# untitled.net
KiCad netlist of a schematic drawn in EAGLE
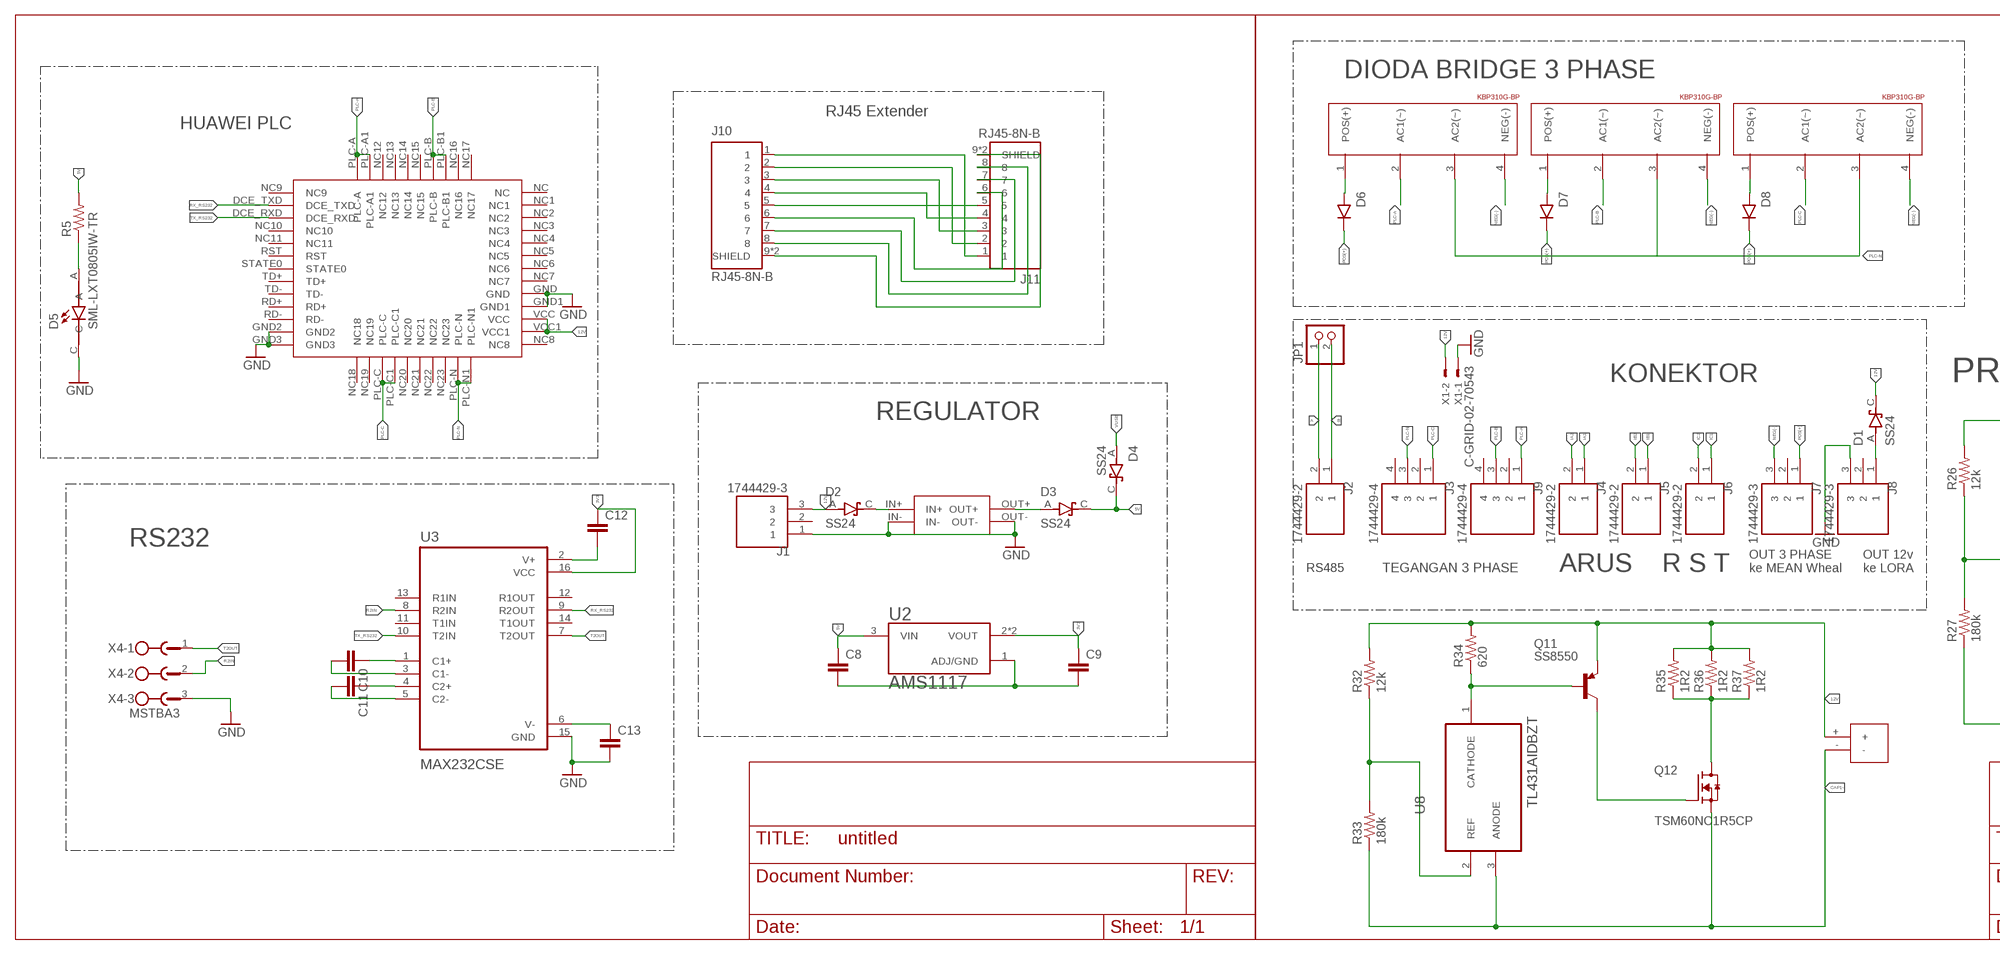
[diagram p0: schematic, sheet 1, part 1 of 2]
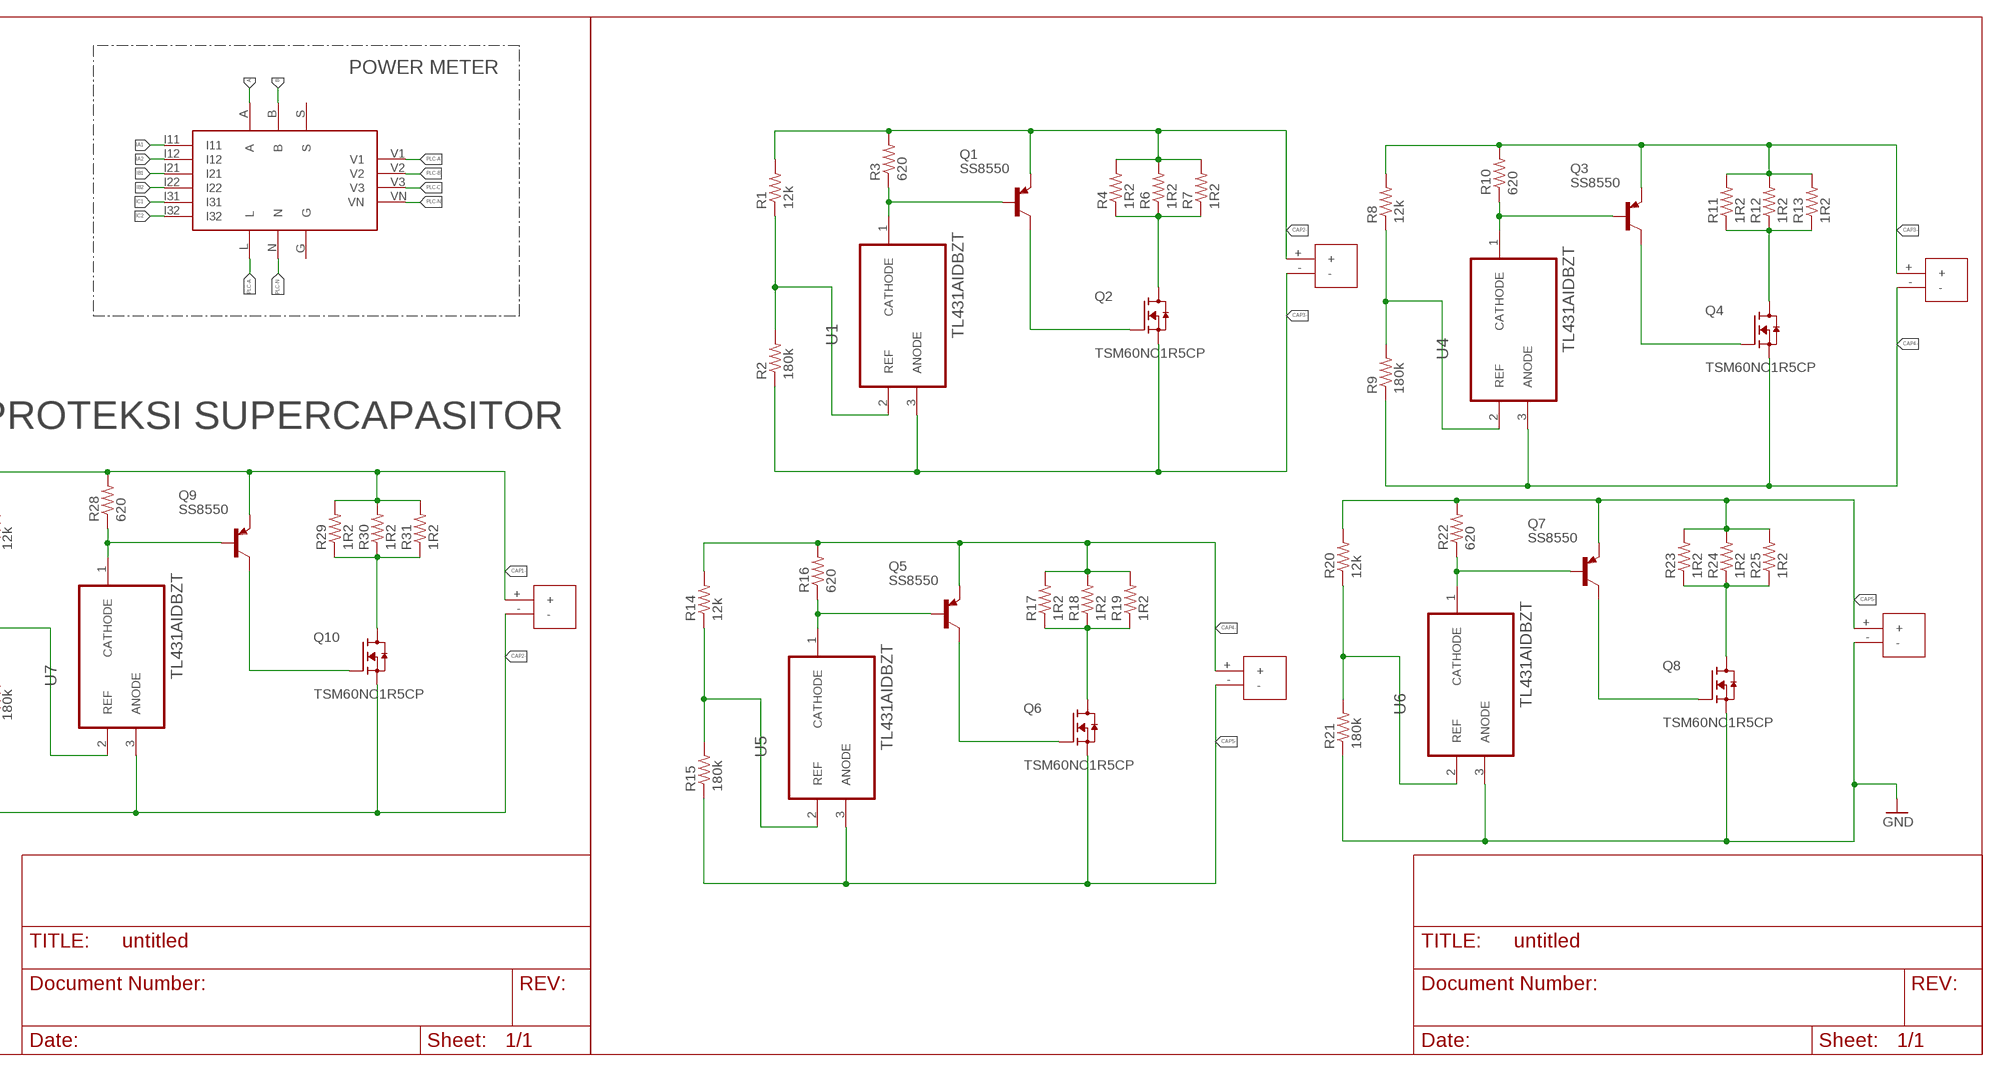
[diagram p1: schematic, sheet 1, part 2 of 2]

(export (version "E")
  (design (tool "Eeschema 10.0.6"))
  (components
    (comp (ref "C8")
      (value "C-EUC0805K")
      (footprint "eagle-import:C0805K")
      (libsource (lib "eagle-import") (part "C-EUC0805K"))
    )
    (comp (ref "C9")
      (value "C-EUC0805K")
      (footprint "eagle-import:C0805K")
      (libsource (lib "eagle-import") (part "C-EUC0805K"))
    )
    (comp (ref "C10")
      (value "C-EUC0805K")
      (footprint "eagle-import:C0805K")
      (libsource (lib "eagle-import") (part "C-EUC0805K"))
    )
    (comp (ref "C11")
      (value "C-EUC0805K")
      (footprint "eagle-import:C0805K")
      (libsource (lib "eagle-import") (part "C-EUC0805K"))
    )
    (comp (ref "C12")
      (value "C-EUC0805K")
      (footprint "eagle-import:C0805K")
      (libsource (lib "eagle-import") (part "C-EUC0805K"))
    )
    (comp (ref "C13")
      (value "C-EUC0805K")
      (footprint "eagle-import:C0805K")
      (libsource (lib "eagle-import") (part "C-EUC0805K"))
    )
    (comp (ref "D1")
      (value "SS24")
      (footprint "eagle-import:DIOM5336X265N")
      (fields (field (name "MF") "ON Semiconductor"))
      (libsource (lib "eagle-import") (part "SS24"))
    )
    (comp (ref "D2")
      (value "SS24")
      (footprint "eagle-import:DIOM5336X265N")
      (fields (field (name "MF") "ON Semiconductor"))
      (libsource (lib "eagle-import") (part "SS24"))
    )
    (comp (ref "D3")
      (value "SS24")
      (footprint "eagle-import:DIOM5336X265N")
      (fields (field (name "MF") "ON Semiconductor"))
      (libsource (lib "eagle-import") (part "SS24"))
    )
    (comp (ref "D4")
      (value "SS24")
      (footprint "eagle-import:DIOM5336X265N")
      (fields (field (name "MF") "ON Semiconductor"))
      (libsource (lib "eagle-import") (part "SS24"))
    )
    (comp (ref "D5")
      (value "SML-LXT0805IW-TR")
      (footprint "eagle-import:LEDC2012X120N")
      (fields (field (name "MF") "Lumex Opto/Components"))
      (libsource (lib "eagle-import") (part "SML-LXT0805IW-TR"))
    )
    (comp (ref "D6")
      (value "1N4001")
      (footprint "eagle-import:DO41-10")
      (fields (field (name "MF") "HVCA"))
      (libsource (lib "eagle-import") (part "1N4001"))
    )
    (comp (ref "D7")
      (value "1N4001")
      (footprint "eagle-import:DO41-10")
      (fields (field (name "MF") "HVCA"))
      (libsource (lib "eagle-import") (part "1N4001"))
    )
    (comp (ref "D8")
      (value "1N4001")
      (footprint "eagle-import:DO41-10")
      (fields (field (name "MF") "HVCA"))
      (libsource (lib "eagle-import") (part "1N4001"))
    )
    (comp (ref "HUAWEI-PLC1")
      (value "HUAWEI-PLC")
      (footprint "eagle-import:HUAWEI-PLC")
      (libsource (lib "eagle-import") (part "HUAWEI-PLC"))
    )
    (comp (ref "J1")
      (value "1744429-3")
      (footprint "eagle-import:TE_1744429-3")
      (fields (field (name "MANUFACTURER") "TE"))
      (libsource (lib "eagle-import") (part "1744429-3"))
    )
    (comp (ref "J2")
      (value "1744429-2")
      (footprint "eagle-import:TE_1744429-2")
      (fields (field (name "MF") "TE Connectivity"))
      (libsource (lib "eagle-import") (part "1744429-2"))
    )
    (comp (ref "J3")
      (value "1744429-4")
      (footprint "eagle-import:TE_1744429-4")
      (fields (field (name "MF") "TE Connectivity"))
      (libsource (lib "eagle-import") (part "1744429-4"))
    )
    (comp (ref "J4")
      (value "1744429-2")
      (footprint "eagle-import:TE_1744429-2")
      (fields (field (name "MF") "TE Connectivity"))
      (libsource (lib "eagle-import") (part "1744429-2"))
    )
    (comp (ref "J5")
      (value "1744429-2")
      (footprint "eagle-import:TE_1744429-2")
      (fields (field (name "MF") "TE Connectivity"))
      (libsource (lib "eagle-import") (part "1744429-2"))
    )
    (comp (ref "J6")
      (value "1744429-2")
      (footprint "eagle-import:TE_1744429-2")
      (fields (field (name "MF") "TE Connectivity"))
      (libsource (lib "eagle-import") (part "1744429-2"))
    )
    (comp (ref "J7")
      (value "1744429-3")
      (footprint "eagle-import:TE_1744429-3")
      (fields (field (name "MANUFACTURER") "TE"))
      (libsource (lib "eagle-import") (part "1744429-3"))
    )
    (comp (ref "J8")
      (value "1744429-3")
      (footprint "eagle-import:TE_1744429-3")
      (fields (field (name "MANUFACTURER") "TE"))
      (libsource (lib "eagle-import") (part "1744429-3"))
    )
    (comp (ref "J9")
      (value "1744429-4")
      (footprint "eagle-import:TE_1744429-4")
      (fields (field (name "MF") "TE Connectivity"))
      (libsource (lib "eagle-import") (part "1744429-4"))
    )
    (comp (ref "J10")
      (value "RJ45-8N-B")
      (footprint "eagle-import:TE_RJ45-8N-B")
      (fields (field (name "MF") "TE Connectivity"))
      (libsource (lib "eagle-import") (part "RJ45-8N-B"))
    )
    (comp (ref "J11")
      (value "RJ45-8N-B")
      (footprint "eagle-import:TE_RJ45-8N-B")
      (fields (field (name "MF") "TE Connectivity"))
      (libsource (lib "eagle-import") (part "RJ45-8N-B"))
    )
    (comp (ref "JP1")
      (value "PINHD-1X2")
      (footprint "eagle-import:1X02")
      (libsource (lib "eagle-import") (part "PINHD-1X2"))
    )
    (comp (ref "MINI1")
      (value "MINI560")
      (footprint "eagle-import:MINI560")
      (libsource (lib "eagle-import") (part "MINI560"))
    )
    (comp (ref "POWERMETER1")
      (value "POWERMETER")
      (footprint "eagle-import:POWERMETER")
      (libsource (lib "eagle-import") (part "POWERMETER"))
    )
    (comp (ref "Q1")
      (value "SS8550")
      (footprint "eagle-import:SOT-23_BEC")
      (fields (field (name "MF") "ON Semiconductor / Fairchild"))
      (libsource (lib "eagle-import") (part "SS8550"))
    )
    (comp (ref "Q2")
      (value "TSM60NC1R5CP")
      (footprint "eagle-import:TRANS_TSM60NC1R5CP")
      (fields (field (name "MF") "Taiwan Semiconductor"))
      (libsource (lib "eagle-import") (part "TSM60NC1R5CP"))
    )
    (comp (ref "Q3")
      (value "SS8550")
      (footprint "eagle-import:SOT-23_BEC")
      (fields (field (name "MF") "ON Semiconductor / Fairchild"))
      (libsource (lib "eagle-import") (part "SS8550"))
    )
    (comp (ref "Q4")
      (value "TSM60NC1R5CP")
      (footprint "eagle-import:TRANS_TSM60NC1R5CP")
      (fields (field (name "MF") "Taiwan Semiconductor"))
      (libsource (lib "eagle-import") (part "TSM60NC1R5CP"))
    )
    (comp (ref "Q5")
      (value "SS8550")
      (footprint "eagle-import:SOT-23_BEC")
      (fields (field (name "MF") "ON Semiconductor / Fairchild"))
      (libsource (lib "eagle-import") (part "SS8550"))
    )
    (comp (ref "Q6")
      (value "TSM60NC1R5CP")
      (footprint "eagle-import:TRANS_TSM60NC1R5CP")
      (fields (field (name "MF") "Taiwan Semiconductor"))
      (libsource (lib "eagle-import") (part "TSM60NC1R5CP"))
    )
    (comp (ref "Q7")
      (value "SS8550")
      (footprint "eagle-import:SOT-23_BEC")
      (fields (field (name "MF") "ON Semiconductor / Fairchild"))
      (libsource (lib "eagle-import") (part "SS8550"))
    )
    (comp (ref "Q8")
      (value "TSM60NC1R5CP")
      (footprint "eagle-import:TRANS_TSM60NC1R5CP")
      (fields (field (name "MF") "Taiwan Semiconductor"))
      (libsource (lib "eagle-import") (part "TSM60NC1R5CP"))
    )
    (comp (ref "Q9")
      (value "SS8550")
      (footprint "eagle-import:SOT-23_BEC")
      (fields (field (name "MF") "ON Semiconductor / Fairchild"))
      (libsource (lib "eagle-import") (part "SS8550"))
    )
    (comp (ref "Q10")
      (value "TSM60NC1R5CP")
      (footprint "eagle-import:TRANS_TSM60NC1R5CP")
      (fields (field (name "MF") "Taiwan Semiconductor"))
      (libsource (lib "eagle-import") (part "TSM60NC1R5CP"))
    )
    (comp (ref "Q11")
      (value "SS8550")
      (footprint "eagle-import:SOT-23_BEC")
      (fields (field (name "MF") "ON Semiconductor / Fairchild"))
      (libsource (lib "eagle-import") (part "SS8550"))
    )
    (comp (ref "Q12")
      (value "TSM60NC1R5CP")
      (footprint "eagle-import:TRANS_TSM60NC1R5CP")
      (fields (field (name "MF") "Taiwan Semiconductor"))
      (libsource (lib "eagle-import") (part "TSM60NC1R5CP"))
    )
    (comp (ref "R1")
      (value "12k")
      (footprint "eagle-import:R0805")
      (libsource (lib "eagle-import") (part "R-US_R0805"))
    )
    (comp (ref "R2")
      (value "180k")
      (footprint "eagle-import:R0805")
      (libsource (lib "eagle-import") (part "R-US_R0805"))
    )
    (comp (ref "R3")
      (value "620")
      (footprint "eagle-import:R0805")
      (libsource (lib "eagle-import") (part "R-US_R0805"))
    )
    (comp (ref "R4")
      (value "1R2")
      (footprint "eagle-import:R2512")
      (libsource (lib "eagle-import") (part "rcl_334_R-US_R2512"))
    )
    (comp (ref "R5")
      (value "R-US_M0805")
      (footprint "eagle-import:M0805")
      (libsource (lib "eagle-import") (part "R-US_M0805"))
    )
    (comp (ref "R6")
      (value "1R2")
      (footprint "eagle-import:R2512")
      (libsource (lib "eagle-import") (part "rcl_334_R-US_R2512"))
    )
    (comp (ref "R7")
      (value "1R2")
      (footprint "eagle-import:R2512")
      (libsource (lib "eagle-import") (part "rcl_334_R-US_R2512"))
    )
    (comp (ref "R8")
      (value "12k")
      (footprint "eagle-import:R0805")
      (libsource (lib "eagle-import") (part "R-US_R0805"))
    )
    (comp (ref "R9")
      (value "180k")
      (footprint "eagle-import:R0805")
      (libsource (lib "eagle-import") (part "R-US_R0805"))
    )
    (comp (ref "R10")
      (value "620")
      (footprint "eagle-import:R0805")
      (libsource (lib "eagle-import") (part "R-US_R0805"))
    )
    (comp (ref "R11")
      (value "1R2")
      (footprint "eagle-import:R2512")
      (libsource (lib "eagle-import") (part "rcl_334_R-US_R2512"))
    )
    (comp (ref "R12")
      (value "1R2")
      (footprint "eagle-import:R2512")
      (libsource (lib "eagle-import") (part "rcl_334_R-US_R2512"))
    )
    (comp (ref "R13")
      (value "1R2")
      (footprint "eagle-import:R2512")
      (libsource (lib "eagle-import") (part "rcl_334_R-US_R2512"))
    )
    (comp (ref "R14")
      (value "12k")
      (footprint "eagle-import:R0805")
      (libsource (lib "eagle-import") (part "R-US_R0805"))
    )
    (comp (ref "R15")
      (value "180k")
      (footprint "eagle-import:R0805")
      (libsource (lib "eagle-import") (part "R-US_R0805"))
    )
    (comp (ref "R16")
      (value "620")
      (footprint "eagle-import:R0805")
      (libsource (lib "eagle-import") (part "R-US_R0805"))
    )
    (comp (ref "R17")
      (value "1R2")
      (footprint "eagle-import:R2512")
      (libsource (lib "eagle-import") (part "rcl_334_R-US_R2512"))
    )
    (comp (ref "R18")
      (value "1R2")
      (footprint "eagle-import:R2512")
      (libsource (lib "eagle-import") (part "rcl_334_R-US_R2512"))
    )
    (comp (ref "R19")
      (value "1R2")
      (footprint "eagle-import:R2512")
      (libsource (lib "eagle-import") (part "rcl_334_R-US_R2512"))
    )
    (comp (ref "R20")
      (value "12k")
      (footprint "eagle-import:R0805")
      (libsource (lib "eagle-import") (part "R-US_R0805"))
    )
    (comp (ref "R21")
      (value "180k")
      (footprint "eagle-import:R0805")
      (libsource (lib "eagle-import") (part "R-US_R0805"))
    )
    (comp (ref "R22")
      (value "620")
      (footprint "eagle-import:R0805")
      (libsource (lib "eagle-import") (part "R-US_R0805"))
    )
    (comp (ref "R23")
      (value "1R2")
      (footprint "eagle-import:R2512")
      (libsource (lib "eagle-import") (part "rcl_334_R-US_R2512"))
    )
    (comp (ref "R24")
      (value "1R2")
      (footprint "eagle-import:R2512")
      (libsource (lib "eagle-import") (part "rcl_334_R-US_R2512"))
    )
    (comp (ref "R25")
      (value "1R2")
      (footprint "eagle-import:R2512")
      (libsource (lib "eagle-import") (part "rcl_334_R-US_R2512"))
    )
    (comp (ref "R26")
      (value "12k")
      (footprint "eagle-import:R0805")
      (libsource (lib "eagle-import") (part "R-US_R0805"))
    )
    (comp (ref "R27")
      (value "180k")
      (footprint "eagle-import:R0805")
      (libsource (lib "eagle-import") (part "R-US_R0805"))
    )
    (comp (ref "R28")
      (value "620")
      (footprint "eagle-import:R0805")
      (libsource (lib "eagle-import") (part "R-US_R0805"))
    )
    (comp (ref "R29")
      (value "1R2")
      (footprint "eagle-import:R2512")
      (libsource (lib "eagle-import") (part "rcl_334_R-US_R2512"))
    )
    (comp (ref "R30")
      (value "1R2")
      (footprint "eagle-import:R2512")
      (libsource (lib "eagle-import") (part "rcl_334_R-US_R2512"))
    )
    (comp (ref "R31")
      (value "1R2")
      (footprint "eagle-import:R2512")
      (libsource (lib "eagle-import") (part "rcl_334_R-US_R2512"))
    )
    (comp (ref "R32")
      (value "12k")
      (footprint "eagle-import:R0805")
      (libsource (lib "eagle-import") (part "R-US_R0805"))
    )
    (comp (ref "R33")
      (value "180k")
      (footprint "eagle-import:R0805")
      (libsource (lib "eagle-import") (part "R-US_R0805"))
    )
    (comp (ref "R34")
      (value "620")
      (footprint "eagle-import:R0805")
      (libsource (lib "eagle-import") (part "R-US_R0805"))
    )
    (comp (ref "R35")
      (value "1R2")
      (footprint "eagle-import:R2512")
      (libsource (lib "eagle-import") (part "rcl_334_R-US_R2512"))
    )
    (comp (ref "R36")
      (value "1R2")
      (footprint "eagle-import:R2512")
      (libsource (lib "eagle-import") (part "rcl_334_R-US_R2512"))
    )
    (comp (ref "R37")
      (value "1R2")
      (footprint "eagle-import:R2512")
      (libsource (lib "eagle-import") (part "rcl_334_R-US_R2512"))
    )
    (comp (ref "SUPERCAP1")
      (value "2.7/500F")
      (footprint "eagle-import:SUPERCAP")
      (libsource (lib "eagle-import") (part "SUPERCAP"))
    )
    (comp (ref "SUPERCAP2")
      (value "2.7/500F")
      (footprint "eagle-import:SUPERCAP")
      (libsource (lib "eagle-import") (part "SUPERCAP"))
    )
    (comp (ref "SUPERCAP3")
      (value "2.7/500F")
      (footprint "eagle-import:SUPERCAP")
      (libsource (lib "eagle-import") (part "SUPERCAP"))
    )
    (comp (ref "SUPERCAP4")
      (value "2.7/500F")
      (footprint "eagle-import:SUPERCAP")
      (libsource (lib "eagle-import") (part "SUPERCAP"))
    )
    (comp (ref "SUPERCAP5")
      (value "2.7/500F")
      (footprint "eagle-import:SUPERCAP")
      (libsource (lib "eagle-import") (part "SUPERCAP"))
    )
    (comp (ref "SUPERCAP6")
      (value "2.7/500F")
      (footprint "eagle-import:SUPERCAP")
      (libsource (lib "eagle-import") (part "SUPERCAP"))
    )
    (comp (ref "U$1")
      (value "KBP310G-BP")
      (footprint "eagle-import:KBP310G-BP")
      (fields (field (name "MF") "Micro Commercial"))
      (libsource (lib "eagle-import") (part "KBP310G-BP"))
    )
    (comp (ref "U$2")
      (value "KBP310G-BP")
      (footprint "eagle-import:KBP310G-BP")
      (fields (field (name "MF") "Micro Commercial"))
      (libsource (lib "eagle-import") (part "KBP310G-BP"))
    )
    (comp (ref "U$3")
      (value "KBP310G-BP")
      (footprint "eagle-import:KBP310G-BP")
      (fields (field (name "MF") "Micro Commercial"))
      (libsource (lib "eagle-import") (part "KBP310G-BP"))
    )
    (comp (ref "U1")
      (value "TL431AIDBZT")
      (footprint "eagle-import:SOT95P237X112-3N")
      (fields (field (name "MF") "Texas Instruments"))
      (libsource (lib "eagle-import") (part "TL431AIDBZT"))
    )
    (comp (ref "U2")
      (value "AMS1117")
      (footprint "eagle-import:SOT229P700X180-4N")
      (fields (field (name "MF") "Advanced Monolithic Systems"))
      (libsource (lib "eagle-import") (part "AMS1117"))
    )
    (comp (ref "U3")
      (value "MAX232CSE")
      (footprint "eagle-import:SOIC127P600X175-16N")
      (fields (field (name "MF") "Maxim Integrated"))
      (libsource (lib "eagle-import") (part "MAX232CSE"))
    )
    (comp (ref "U4")
      (value "TL431AIDBZT")
      (footprint "eagle-import:SOT95P237X112-3N")
      (fields (field (name "MF") "Texas Instruments"))
      (libsource (lib "eagle-import") (part "TL431AIDBZT"))
    )
    (comp (ref "U5")
      (value "TL431AIDBZT")
      (footprint "eagle-import:SOT95P237X112-3N")
      (fields (field (name "MF") "Texas Instruments"))
      (libsource (lib "eagle-import") (part "TL431AIDBZT"))
    )
    (comp (ref "U6")
      (value "TL431AIDBZT")
      (footprint "eagle-import:SOT95P237X112-3N")
      (fields (field (name "MF") "Texas Instruments"))
      (libsource (lib "eagle-import") (part "TL431AIDBZT"))
    )
    (comp (ref "U7")
      (value "TL431AIDBZT")
      (footprint "eagle-import:SOT95P237X112-3N")
      (fields (field (name "MF") "Texas Instruments"))
      (libsource (lib "eagle-import") (part "TL431AIDBZT"))
    )
    (comp (ref "U8")
      (value "TL431AIDBZT")
      (footprint "eagle-import:SOT95P237X112-3N")
      (fields (field (name "MF") "Texas Instruments"))
      (libsource (lib "eagle-import") (part "TL431AIDBZT"))
    )
    (comp (ref "X1")
      (value "C-GRID-02-70543")
      (footprint "eagle-import:70543-02")
      (fields (field (name "MF") "MOLEX"))
      (libsource (lib "eagle-import") (part "C-GRID-02-70543"))
    )
    (comp (ref "X4")
      (value "MSTBA3")
      (footprint "eagle-import:MSTBA3")
      (fields (field (name "MF") "FARNELL") (field (name "MPN") "1757255"))
      (libsource (lib "eagle-import") (part "MSTBA3"))
    )
  )
  (nets
    (net (code "1") (name "3V3") (class "Default")
      (node (ref "C12") (pin "1") (pinfunction "1_1") (pintype "passive"))
      (node (ref "C9") (pin "1") (pinfunction "1_1") (pintype "passive"))
      (node (ref "U2") (pin "2") (pinfunction "VOUT_2") (pintype "output"))
      (node (ref "U2") (pin "4") (pinfunction "VOUT_4") (pintype "output"))
      (node (ref "U3") (pin "16") (pinfunction "VCC_16") (pintype "power_in"))
    )
    (net (code "2") (name "5V") (class "Default")
      (node (ref "C8") (pin "1") (pinfunction "1_1") (pintype "passive"))
      (node (ref "D3") (pin "C") (pinfunction "K_C") (pintype "passive"))
      (node (ref "D4") (pin "C") (pinfunction "K_C") (pintype "passive"))
      (node (ref "R5") (pin "2") (pinfunction "2_2") (pintype "passive"))
      (node (ref "U2") (pin "3") (pinfunction "VIN_3") (pintype "input"))
    )
    (net (code "3") (name "12V") (class "Default")
      (node (ref "D1") (pin "C") (pinfunction "K_C") (pintype "passive"))
      (node (ref "D2") (pin "A") (pinfunction "A_A") (pintype "passive"))
      (node (ref "HUAWEI-PLC1") (pin "VCC") (pinfunction "VCC_VCC") (pintype "bidirectional"))
      (node (ref "HUAWEI-PLC1") (pin "VCC1") (pinfunction "VCC1_VCC1") (pintype "bidirectional"))
      (node (ref "J1") (pin "3") (pinfunction "3_3") (pintype "passive"))
      (node (ref "Q11") (pin "E") (pinfunction "E_E") (pintype "passive"))
      (node (ref "R32") (pin "2") (pinfunction "2_2") (pintype "passive"))
      (node (ref "R34") (pin "2") (pinfunction "2_2") (pintype "passive"))
      (node (ref "R35") (pin "2") (pinfunction "2_2") (pintype "passive"))
      (node (ref "R36") (pin "2") (pinfunction "2_2") (pintype "passive"))
      (node (ref "R37") (pin "2") (pinfunction "2_2") (pintype "passive"))
      (node (ref "SUPERCAP6") (pin "+") (pinfunction "+_+") (pintype "bidirectional"))
      (node (ref "X1") (pin "2") (pinfunction "S_2") (pintype "passive"))
    )
    (net (code "4") (name "A") (class "Default")
      (node (ref "J2") (pin "2") (pinfunction "2_2") (pintype "passive"))
      (node (ref "JP1") (pin "1") (pinfunction "1_1") (pintype "passive"))
      (node (ref "POWERMETER1") (pin "A") (pinfunction "A_A") (pintype "bidirectional"))
    )
    (net (code "5") (name "B") (class "Default")
      (node (ref "J2") (pin "1") (pinfunction "1_1") (pintype "passive"))
      (node (ref "JP1") (pin "2") (pinfunction "2_2") (pintype "passive"))
      (node (ref "POWERMETER1") (pin "B") (pinfunction "B_B") (pintype "bidirectional"))
    )
    (net (code "6") (name "CAP1-") (class "Default")
      (node (ref "Q12") (pin "3") (pinfunction "S_3") (pintype "passive"))
      (node (ref "Q9") (pin "E") (pinfunction "E_E") (pintype "passive"))
      (node (ref "R26") (pin "2") (pinfunction "2_2") (pintype "passive"))
      (node (ref "R28") (pin "2") (pinfunction "2_2") (pintype "passive"))
      (node (ref "R29") (pin "2") (pinfunction "2_2") (pintype "passive"))
      (node (ref "R30") (pin "2") (pinfunction "2_2") (pintype "passive"))
      (node (ref "R31") (pin "2") (pinfunction "2_2") (pintype "passive"))
      (node (ref "R33") (pin "1") (pinfunction "1_1") (pintype "passive"))
      (node (ref "SUPERCAP5") (pin "+") (pinfunction "+_+") (pintype "bidirectional"))
      (node (ref "SUPERCAP6") (pin "-") (pinfunction "-_-") (pintype "bidirectional"))
      (node (ref "U8") (pin "3") (pinfunction "ANODE_3") (pintype "passive"))
    )
    (net (code "7") (name "CAP2-") (class "Default")
      (node (ref "Q1") (pin "E") (pinfunction "E_E") (pintype "passive"))
      (node (ref "Q10") (pin "3") (pinfunction "S_3") (pintype "passive"))
      (node (ref "R1") (pin "2") (pinfunction "2_2") (pintype "passive"))
      (node (ref "R27") (pin "1") (pinfunction "1_1") (pintype "passive"))
      (node (ref "R3") (pin "2") (pinfunction "2_2") (pintype "passive"))
      (node (ref "R4") (pin "2") (pinfunction "2_2") (pintype "passive"))
      (node (ref "R6") (pin "2") (pinfunction "2_2") (pintype "passive"))
      (node (ref "R7") (pin "2") (pinfunction "2_2") (pintype "passive"))
      (node (ref "SUPERCAP1") (pin "+") (pinfunction "+_+") (pintype "bidirectional"))
      (node (ref "SUPERCAP5") (pin "-") (pinfunction "-_-") (pintype "bidirectional"))
      (node (ref "U7") (pin "3") (pinfunction "ANODE_3") (pintype "passive"))
    )
    (net (code "8") (name "CAP3-") (class "Default")
      (node (ref "Q2") (pin "3") (pinfunction "S_3") (pintype "passive"))
      (node (ref "Q3") (pin "E") (pinfunction "E_E") (pintype "passive"))
      (node (ref "R10") (pin "2") (pinfunction "2_2") (pintype "passive"))
      (node (ref "R11") (pin "2") (pinfunction "2_2") (pintype "passive"))
      (node (ref "R12") (pin "2") (pinfunction "2_2") (pintype "passive"))
      (node (ref "R13") (pin "2") (pinfunction "2_2") (pintype "passive"))
      (node (ref "R2") (pin "1") (pinfunction "1_1") (pintype "passive"))
      (node (ref "R8") (pin "2") (pinfunction "2_2") (pintype "passive"))
      (node (ref "SUPERCAP1") (pin "-") (pinfunction "-_-") (pintype "bidirectional"))
      (node (ref "SUPERCAP2") (pin "+") (pinfunction "+_+") (pintype "bidirectional"))
      (node (ref "U1") (pin "3") (pinfunction "ANODE_3") (pintype "passive"))
    )
    (net (code "9") (name "CAP4-") (class "Default")
      (node (ref "Q4") (pin "3") (pinfunction "S_3") (pintype "passive"))
      (node (ref "Q5") (pin "E") (pinfunction "E_E") (pintype "passive"))
      (node (ref "R14") (pin "2") (pinfunction "2_2") (pintype "passive"))
      (node (ref "R16") (pin "2") (pinfunction "2_2") (pintype "passive"))
      (node (ref "R17") (pin "2") (pinfunction "2_2") (pintype "passive"))
      (node (ref "R18") (pin "2") (pinfunction "2_2") (pintype "passive"))
      (node (ref "R19") (pin "2") (pinfunction "2_2") (pintype "passive"))
      (node (ref "R9") (pin "1") (pinfunction "1_1") (pintype "passive"))
      (node (ref "SUPERCAP2") (pin "-") (pinfunction "-_-") (pintype "bidirectional"))
      (node (ref "SUPERCAP3") (pin "+") (pinfunction "+_+") (pintype "bidirectional"))
      (node (ref "U4") (pin "3") (pinfunction "ANODE_3") (pintype "passive"))
    )
    (net (code "10") (name "CAP5-") (class "Default")
      (node (ref "Q6") (pin "3") (pinfunction "S_3") (pintype "passive"))
      (node (ref "Q7") (pin "E") (pinfunction "E_E") (pintype "passive"))
      (node (ref "R15") (pin "1") (pinfunction "1_1") (pintype "passive"))
      (node (ref "R20") (pin "2") (pinfunction "2_2") (pintype "passive"))
      (node (ref "R22") (pin "2") (pinfunction "2_2") (pintype "passive"))
      (node (ref "R23") (pin "2") (pinfunction "2_2") (pintype "passive"))
      (node (ref "R24") (pin "2") (pinfunction "2_2") (pintype "passive"))
      (node (ref "R25") (pin "2") (pinfunction "2_2") (pintype "passive"))
      (node (ref "SUPERCAP3") (pin "-") (pinfunction "-_-") (pintype "bidirectional"))
      (node (ref "SUPERCAP4") (pin "+") (pinfunction "+_+") (pintype "bidirectional"))
      (node (ref "U5") (pin "3") (pinfunction "ANODE_3") (pintype "passive"))
    )
    (net (code "11") (name "GND") (class "Default")
      (node (ref "C13") (pin "2") (pinfunction "2_2") (pintype "passive"))
      (node (ref "D5") (pin "C") (pinfunction "C_C") (pintype "passive"))
      (node (ref "HUAWEI-PLC1") (pin "GND") (pinfunction "GND_GND") (pintype "bidirectional"))
      (node (ref "HUAWEI-PLC1") (pin "GND1") (pinfunction "GND1_GND1") (pintype "bidirectional"))
      (node (ref "HUAWEI-PLC1") (pin "GND2") (pinfunction "GND2_GND2") (pintype "bidirectional"))
      (node (ref "HUAWEI-PLC1") (pin "GND3") (pinfunction "GND3_GND3") (pintype "bidirectional"))
      (node (ref "J1") (pin "1") (pinfunction "1_1") (pintype "passive"))
      (node (ref "J8") (pin "3") (pinfunction "3_3") (pintype "passive"))
      (node (ref "MINI1") (pin "IN-") (pinfunction "IN-_IN-") (pintype "bidirectional"))
      (node (ref "MINI1") (pin "OUT-") (pinfunction "OUT-_OUT-") (pintype "bidirectional"))
      (node (ref "Q8") (pin "3") (pinfunction "S_3") (pintype "passive"))
      (node (ref "R21") (pin "1") (pinfunction "1_1") (pintype "passive"))
      (node (ref "SUPERCAP4") (pin "-") (pinfunction "-_-") (pintype "bidirectional"))
      (node (ref "U3") (pin "15") (pinfunction "GND_15") (pintype "power_in"))
      (node (ref "U6") (pin "3") (pinfunction "ANODE_3") (pintype "passive"))
      (node (ref "X1") (pin "1") (pinfunction "S_1") (pintype "passive"))
      (node (ref "X4") (pin "3") (pinfunction "1_3") (pintype "passive"))
    )
    (net (code "12") (name "IA1") (class "Default")
      (node (ref "J4") (pin "1") (pinfunction "1_1") (pintype "passive"))
      (node (ref "POWERMETER1") (pin "I11") (pinfunction "I11_I11") (pintype "bidirectional"))
    )
    (net (code "13") (name "IA2") (class "Default")
      (node (ref "J4") (pin "2") (pinfunction "2_2") (pintype "passive"))
      (node (ref "POWERMETER1") (pin "I12") (pinfunction "I12_I12") (pintype "bidirectional"))
    )
    (net (code "14") (name "IB1") (class "Default")
      (node (ref "J5") (pin "1") (pinfunction "1_1") (pintype "passive"))
      (node (ref "POWERMETER1") (pin "I21") (pinfunction "I21_I21") (pintype "bidirectional"))
    )
    (net (code "15") (name "IB2") (class "Default")
      (node (ref "J5") (pin "2") (pinfunction "2_2") (pintype "passive"))
      (node (ref "POWERMETER1") (pin "I22") (pinfunction "I22_I22") (pintype "bidirectional"))
    )
    (net (code "16") (name "IC1") (class "Default")
      (node (ref "J6") (pin "1") (pinfunction "1_1") (pintype "passive"))
      (node (ref "POWERMETER1") (pin "I31") (pinfunction "I31_I31") (pintype "bidirectional"))
    )
    (net (code "17") (name "IC2") (class "Default")
      (node (ref "J6") (pin "2") (pinfunction "2_2") (pintype "passive"))
      (node (ref "POWERMETER1") (pin "I32") (pinfunction "I32_I32") (pintype "bidirectional"))
    )
    (net (code "18") (name "NEG(-)") (class "Default")
      (node (ref "J7") (pin "3") (pinfunction "3_3") (pintype "passive"))
      (node (ref "U$1") (pin "4") (pinfunction "NEG(-)_4") (pintype "bidirectional"))
      (node (ref "U$2") (pin "4") (pinfunction "NEG(-)_4") (pintype "bidirectional"))
      (node (ref "U$3") (pin "4") (pinfunction "NEG(-)_4") (pintype "bidirectional"))
    )
    (net (code "19") (name "Net-(D1-PadA)") (class "Default")
      (node (ref "D1") (pin "A") (pinfunction "A_A") (pintype "passive"))
      (node (ref "J8") (pin "1") (pinfunction "1_1") (pintype "passive"))
    )
    (net (code "20") (name "Net-(D2-K)") (class "Default")
      (node (ref "D2") (pin "C") (pinfunction "K_C") (pintype "passive"))
      (node (ref "MINI1") (pin "IN+") (pinfunction "IN+_IN+") (pintype "bidirectional"))
    )
    (net (code "21") (name "Net-(D3-PadA)") (class "Default")
      (node (ref "D3") (pin "A") (pinfunction "A_A") (pintype "passive"))
      (node (ref "MINI1") (pin "OUT+") (pinfunction "OUT+_OUT+") (pintype "bidirectional"))
    )
    (net (code "22") (name "Net-(D5-PadA)") (class "Default")
      (node (ref "D5") (pin "A") (pinfunction "A_A") (pintype "passive"))
      (node (ref "R5") (pin "1") (pinfunction "1_1") (pintype "passive"))
    )
    (net (code "23") (name "Net-(D6-ANODE)") (class "Default")
      (node (ref "D6") (pin "A") (pinfunction "ANODE_A") (pintype "passive"))
      (node (ref "U$1") (pin "1") (pinfunction "POS(+)_1") (pintype "bidirectional"))
    )
    (net (code "24") (name "Net-(D7-ANODE)") (class "Default")
      (node (ref "D7") (pin "A") (pinfunction "ANODE_A") (pintype "passive"))
      (node (ref "U$2") (pin "1") (pinfunction "POS(+)_1") (pintype "bidirectional"))
    )
    (net (code "25") (name "Net-(D8-ANODE)") (class "Default")
      (node (ref "D8") (pin "A") (pinfunction "ANODE_A") (pintype "passive"))
      (node (ref "U$3") (pin "1") (pinfunction "POS(+)_1") (pintype "bidirectional"))
    )
    (net (code "26") (name "Net-(J10-Pad1)") (class "Default")
      (node (ref "J10") (pin "1") (pinfunction "1_1") (pintype "passive"))
      (node (ref "J11") (pin "1") (pinfunction "1_1") (pintype "passive"))
    )
    (net (code "27") (name "Net-(J10-Pad2)") (class "Default")
      (node (ref "J10") (pin "2") (pinfunction "2_2") (pintype "passive"))
      (node (ref "J11") (pin "2") (pinfunction "2_2") (pintype "passive"))
    )
    (net (code "28") (name "Net-(J10-Pad3)") (class "Default")
      (node (ref "J10") (pin "3") (pinfunction "3_3") (pintype "passive"))
      (node (ref "J11") (pin "3") (pinfunction "3_3") (pintype "passive"))
    )
    (net (code "29") (name "Net-(J10-Pad4)") (class "Default")
      (node (ref "J10") (pin "4") (pinfunction "4_4") (pintype "passive"))
      (node (ref "J11") (pin "4") (pinfunction "4_4") (pintype "passive"))
    )
    (net (code "30") (name "Net-(J10-Pad5)") (class "Default")
      (node (ref "J10") (pin "5") (pinfunction "5_5") (pintype "passive"))
      (node (ref "J11") (pin "5") (pinfunction "5_5") (pintype "passive"))
    )
    (net (code "31") (name "Net-(J10-Pad6)") (class "Default")
      (node (ref "J10") (pin "6") (pinfunction "6_6") (pintype "passive"))
      (node (ref "J11") (pin "6") (pinfunction "6_6") (pintype "passive"))
    )
    (net (code "32") (name "Net-(J10-Pad7)") (class "Default")
      (node (ref "J10") (pin "7") (pinfunction "7_7") (pintype "passive"))
      (node (ref "J11") (pin "7") (pinfunction "7_7") (pintype "passive"))
    )
    (net (code "33") (name "Net-(J10-Pad8)") (class "Default")
      (node (ref "J10") (pin "8") (pinfunction "8_8") (pintype "passive"))
      (node (ref "J11") (pin "8") (pinfunction "8_8") (pintype "passive"))
    )
    (net (code "34") (name "Net-(J10-SHIELD-Pad10)") (class "Default")
      (node (ref "J10") (pin "10") (pinfunction "SHIELD_10") (pintype "passive"))
      (node (ref "J10") (pin "9") (pinfunction "SHIELD_9") (pintype "passive"))
      (node (ref "J11") (pin "10") (pinfunction "SHIELD_10") (pintype "passive"))
      (node (ref "J11") (pin "9") (pinfunction "SHIELD_9") (pintype "passive"))
    )
    (net (code "35") (name "Net-(Q2-D)") (class "Default")
      (node (ref "Q2") (pin "2") (pinfunction "D_2") (pintype "passive"))
      (node (ref "R4") (pin "1") (pinfunction "1_1") (pintype "passive"))
      (node (ref "R6") (pin "1") (pinfunction "1_1") (pintype "passive"))
      (node (ref "R7") (pin "1") (pinfunction "1_1") (pintype "passive"))
    )
    (net (code "36") (name "Net-(Q2-G)") (class "Default")
      (node (ref "Q1") (pin "C") (pinfunction "C_C") (pintype "passive"))
      (node (ref "Q2") (pin "1") (pinfunction "G_1") (pintype "passive"))
    )
    (net (code "37") (name "Net-(Q4-D)") (class "Default")
      (node (ref "Q4") (pin "2") (pinfunction "D_2") (pintype "passive"))
      (node (ref "R11") (pin "1") (pinfunction "1_1") (pintype "passive"))
      (node (ref "R12") (pin "1") (pinfunction "1_1") (pintype "passive"))
      (node (ref "R13") (pin "1") (pinfunction "1_1") (pintype "passive"))
    )
    (net (code "38") (name "Net-(Q4-G)") (class "Default")
      (node (ref "Q3") (pin "C") (pinfunction "C_C") (pintype "passive"))
      (node (ref "Q4") (pin "1") (pinfunction "G_1") (pintype "passive"))
    )
    (net (code "39") (name "Net-(Q6-D)") (class "Default")
      (node (ref "Q6") (pin "2") (pinfunction "D_2") (pintype "passive"))
      (node (ref "R17") (pin "1") (pinfunction "1_1") (pintype "passive"))
      (node (ref "R18") (pin "1") (pinfunction "1_1") (pintype "passive"))
      (node (ref "R19") (pin "1") (pinfunction "1_1") (pintype "passive"))
    )
    (net (code "40") (name "Net-(Q6-G)") (class "Default")
      (node (ref "Q5") (pin "C") (pinfunction "C_C") (pintype "passive"))
      (node (ref "Q6") (pin "1") (pinfunction "G_1") (pintype "passive"))
    )
    (net (code "41") (name "Net-(Q8-D)") (class "Default")
      (node (ref "Q8") (pin "2") (pinfunction "D_2") (pintype "passive"))
      (node (ref "R23") (pin "1") (pinfunction "1_1") (pintype "passive"))
      (node (ref "R24") (pin "1") (pinfunction "1_1") (pintype "passive"))
      (node (ref "R25") (pin "1") (pinfunction "1_1") (pintype "passive"))
    )
    (net (code "42") (name "Net-(Q8-G)") (class "Default")
      (node (ref "Q7") (pin "C") (pinfunction "C_C") (pintype "passive"))
      (node (ref "Q8") (pin "1") (pinfunction "G_1") (pintype "passive"))
    )
    (net (code "43") (name "Net-(Q10-D)") (class "Default")
      (node (ref "Q10") (pin "2") (pinfunction "D_2") (pintype "passive"))
      (node (ref "R29") (pin "1") (pinfunction "1_1") (pintype "passive"))
      (node (ref "R30") (pin "1") (pinfunction "1_1") (pintype "passive"))
      (node (ref "R31") (pin "1") (pinfunction "1_1") (pintype "passive"))
    )
    (net (code "44") (name "Net-(Q10-G)") (class "Default")
      (node (ref "Q10") (pin "1") (pinfunction "G_1") (pintype "passive"))
      (node (ref "Q9") (pin "C") (pinfunction "C_C") (pintype "passive"))
    )
    (net (code "45") (name "Net-(Q12-D)") (class "Default")
      (node (ref "Q12") (pin "2") (pinfunction "D_2") (pintype "passive"))
      (node (ref "R35") (pin "1") (pinfunction "1_1") (pintype "passive"))
      (node (ref "R36") (pin "1") (pinfunction "1_1") (pintype "passive"))
      (node (ref "R37") (pin "1") (pinfunction "1_1") (pintype "passive"))
    )
    (net (code "46") (name "Net-(Q12-G)") (class "Default")
      (node (ref "Q11") (pin "C") (pinfunction "C_C") (pintype "passive"))
      (node (ref "Q12") (pin "1") (pinfunction "G_1") (pintype "passive"))
    )
    (net (code "47") (name "Net-(U1-CATHODE)") (class "Default")
      (node (ref "Q1") (pin "B") (pinfunction "B_B") (pintype "passive"))
      (node (ref "R3") (pin "1") (pinfunction "1_1") (pintype "passive"))
      (node (ref "U1") (pin "1") (pinfunction "CATHODE_1") (pintype "passive"))
    )
    (net (code "48") (name "Net-(U1-REF)") (class "Default")
      (node (ref "R1") (pin "1") (pinfunction "1_1") (pintype "passive"))
      (node (ref "R2") (pin "2") (pinfunction "2_2") (pintype "passive"))
      (node (ref "U1") (pin "2") (pinfunction "REF_2") (pintype "power_in"))
    )
    (net (code "49") (name "Net-(U2-ADJ{slash}GND)") (class "Default")
      (node (ref "C8") (pin "2") (pinfunction "2_2") (pintype "passive"))
      (node (ref "C9") (pin "2") (pinfunction "2_2") (pintype "passive"))
      (node (ref "U2") (pin "1") (pinfunction "ADJ/GND_1") (pintype "power_in"))
    )
    (net (code "50") (name "Net-(U3-C1+)") (class "Default")
      (node (ref "C10") (pin "1") (pinfunction "1_1") (pintype "passive"))
      (node (ref "U3") (pin "1") (pinfunction "C1+_1") (pintype "bidirectional"))
    )
    (net (code "51") (name "Net-(U3-C1-)") (class "Default")
      (node (ref "C10") (pin "2") (pinfunction "2_2") (pintype "passive"))
      (node (ref "U3") (pin "3") (pinfunction "C1-_3") (pintype "bidirectional"))
    )
    (net (code "52") (name "Net-(U3-C2+)") (class "Default")
      (node (ref "C11") (pin "1") (pinfunction "1_1") (pintype "passive"))
      (node (ref "U3") (pin "4") (pinfunction "C2+_4") (pintype "bidirectional"))
    )
    (net (code "53") (name "Net-(U3-C2-)") (class "Default")
      (node (ref "C11") (pin "2") (pinfunction "2_2") (pintype "passive"))
      (node (ref "U3") (pin "5") (pinfunction "C2-_5") (pintype "bidirectional"))
    )
    (net (code "54") (name "Net-(U3-V+)") (class "Default")
      (node (ref "C12") (pin "2") (pinfunction "2_2") (pintype "passive"))
      (node (ref "U3") (pin "2") (pinfunction "V+_2") (pintype "power_in"))
    )
    (net (code "55") (name "Net-(U3-V-)") (class "Default")
      (node (ref "C13") (pin "1") (pinfunction "1_1") (pintype "passive"))
      (node (ref "U3") (pin "6") (pinfunction "V-_6") (pintype "power_in"))
    )
    (net (code "56") (name "Net-(U4-CATHODE)") (class "Default")
      (node (ref "Q3") (pin "B") (pinfunction "B_B") (pintype "passive"))
      (node (ref "R10") (pin "1") (pinfunction "1_1") (pintype "passive"))
      (node (ref "U4") (pin "1") (pinfunction "CATHODE_1") (pintype "passive"))
    )
    (net (code "57") (name "Net-(U4-REF)") (class "Default")
      (node (ref "R8") (pin "1") (pinfunction "1_1") (pintype "passive"))
      (node (ref "R9") (pin "2") (pinfunction "2_2") (pintype "passive"))
      (node (ref "U4") (pin "2") (pinfunction "REF_2") (pintype "power_in"))
    )
    (net (code "58") (name "Net-(U5-CATHODE)") (class "Default")
      (node (ref "Q5") (pin "B") (pinfunction "B_B") (pintype "passive"))
      (node (ref "R16") (pin "1") (pinfunction "1_1") (pintype "passive"))
      (node (ref "U5") (pin "1") (pinfunction "CATHODE_1") (pintype "passive"))
    )
    (net (code "59") (name "Net-(U5-REF)") (class "Default")
      (node (ref "R14") (pin "1") (pinfunction "1_1") (pintype "passive"))
      (node (ref "R15") (pin "2") (pinfunction "2_2") (pintype "passive"))
      (node (ref "U5") (pin "2") (pinfunction "REF_2") (pintype "power_in"))
    )
    (net (code "60") (name "Net-(U6-CATHODE)") (class "Default")
      (node (ref "Q7") (pin "B") (pinfunction "B_B") (pintype "passive"))
      (node (ref "R22") (pin "1") (pinfunction "1_1") (pintype "passive"))
      (node (ref "U6") (pin "1") (pinfunction "CATHODE_1") (pintype "passive"))
    )
    (net (code "61") (name "Net-(U6-REF)") (class "Default")
      (node (ref "R20") (pin "1") (pinfunction "1_1") (pintype "passive"))
      (node (ref "R21") (pin "2") (pinfunction "2_2") (pintype "passive"))
      (node (ref "U6") (pin "2") (pinfunction "REF_2") (pintype "power_in"))
    )
    (net (code "62") (name "Net-(U7-CATHODE)") (class "Default")
      (node (ref "Q9") (pin "B") (pinfunction "B_B") (pintype "passive"))
      (node (ref "R28") (pin "1") (pinfunction "1_1") (pintype "passive"))
      (node (ref "U7") (pin "1") (pinfunction "CATHODE_1") (pintype "passive"))
    )
    (net (code "63") (name "Net-(U7-REF)") (class "Default")
      (node (ref "R26") (pin "1") (pinfunction "1_1") (pintype "passive"))
      (node (ref "R27") (pin "2") (pinfunction "2_2") (pintype "passive"))
      (node (ref "U7") (pin "2") (pinfunction "REF_2") (pintype "power_in"))
    )
    (net (code "64") (name "Net-(U8-CATHODE)") (class "Default")
      (node (ref "Q11") (pin "B") (pinfunction "B_B") (pintype "passive"))
      (node (ref "R34") (pin "1") (pinfunction "1_1") (pintype "passive"))
      (node (ref "U8") (pin "1") (pinfunction "CATHODE_1") (pintype "passive"))
    )
    (net (code "65") (name "Net-(U8-REF)") (class "Default")
      (node (ref "R32") (pin "1") (pinfunction "1_1") (pintype "passive"))
      (node (ref "R33") (pin "2") (pinfunction "2_2") (pintype "passive"))
      (node (ref "U8") (pin "2") (pinfunction "REF_2") (pintype "power_in"))
    )
    (net (code "66") (name "PLC-A") (class "Default")
      (node (ref "HUAWEI-PLC1") (pin "PLC-A") (pinfunction "PLC-A_PLC-A") (pintype "bidirectional"))
      (node (ref "HUAWEI-PLC1") (pin "PLC-A1") (pinfunction "PLC-A1_PLC-A1") (pintype "bidirectional"))
      (node (ref "J9") (pin "1") (pinfunction "1_1") (pintype "passive"))
      (node (ref "POWERMETER1") (pin "L") (pinfunction "L_L") (pintype "bidirectional"))
      (node (ref "POWERMETER1") (pin "V1") (pinfunction "V1_V1") (pintype "bidirectional"))
      (node (ref "U$1") (pin "2") (pinfunction "AC1(~{})_2") (pintype "bidirectional"))
    )
    (net (code "67") (name "PLC-B") (class "Default")
      (node (ref "HUAWEI-PLC1") (pin "PLC-B") (pinfunction "PLC-B_PLC-B") (pintype "bidirectional"))
      (node (ref "HUAWEI-PLC1") (pin "PLC-B1") (pinfunction "PLC-B1_PLC-B1") (pintype "bidirectional"))
      (node (ref "J9") (pin "3") (pinfunction "3_3") (pintype "passive"))
      (node (ref "POWERMETER1") (pin "V2") (pinfunction "V2_V2") (pintype "bidirectional"))
      (node (ref "U$2") (pin "2") (pinfunction "AC1(~{})_2") (pintype "bidirectional"))
    )
    (net (code "68") (name "PLC-C") (class "Default")
      (node (ref "HUAWEI-PLC1") (pin "PLC-C") (pinfunction "PLC-C_PLC-C") (pintype "bidirectional"))
      (node (ref "HUAWEI-PLC1") (pin "PLC-C1") (pinfunction "PLC-C1_PLC-C1") (pintype "bidirectional"))
      (node (ref "J3") (pin "1") (pinfunction "1_1") (pintype "passive"))
      (node (ref "POWERMETER1") (pin "V3") (pinfunction "V3_V3") (pintype "bidirectional"))
      (node (ref "U$3") (pin "2") (pinfunction "AC1(~{})_2") (pintype "bidirectional"))
    )
    (net (code "69") (name "PLC-N") (class "Default")
      (node (ref "HUAWEI-PLC1") (pin "PLC-N") (pinfunction "PLC-N_PLC-N") (pintype "bidirectional"))
      (node (ref "HUAWEI-PLC1") (pin "PLC-N1") (pinfunction "PLC-N1_PLC-N1") (pintype "bidirectional"))
      (node (ref "J3") (pin "3") (pinfunction "3_3") (pintype "passive"))
      (node (ref "POWERMETER1") (pin "N") (pinfunction "N_N") (pintype "bidirectional"))
      (node (ref "POWERMETER1") (pin "VN") (pinfunction "VN_VN") (pintype "bidirectional"))
      (node (ref "U$1") (pin "3") (pinfunction "AC2(~{})_3") (pintype "bidirectional"))
      (node (ref "U$2") (pin "3") (pinfunction "AC2(~{})_3") (pintype "bidirectional"))
      (node (ref "U$3") (pin "3") (pinfunction "AC2(~{})_3") (pintype "bidirectional"))
    )
    (net (code "70") (name "POS(+)") (class "Default")
      (node (ref "D6") (pin "C") (pinfunction "CATHODE_C") (pintype "passive"))
      (node (ref "D7") (pin "C") (pinfunction "CATHODE_C") (pintype "passive"))
      (node (ref "D8") (pin "C") (pinfunction "CATHODE_C") (pintype "passive"))
      (node (ref "J7") (pin "1") (pinfunction "1_1") (pintype "passive"))
    )
    (net (code "71") (name "R2IN") (class "Default")
      (node (ref "U3") (pin "8") (pinfunction "R2IN_8") (pintype "input"))
      (node (ref "X4") (pin "2") (pinfunction "1_2") (pintype "passive"))
    )
    (net (code "72") (name "RX_RS232") (class "Default")
      (node (ref "HUAWEI-PLC1") (pin "DCE_TXD") (pinfunction "DCE_TXD_DCE_TXD") (pintype "bidirectional"))
      (node (ref "U3") (pin "9") (pinfunction "R2OUT_9") (pintype "output"))
    )
    (net (code "73") (name "T2OUT") (class "Default")
      (node (ref "U3") (pin "7") (pinfunction "T2OUT_7") (pintype "output"))
      (node (ref "X4") (pin "1") (pinfunction "1_1") (pintype "passive"))
    )
    (net (code "74") (name "TX_RS232") (class "Default")
      (node (ref "HUAWEI-PLC1") (pin "DCE_RXD") (pinfunction "DCE_RXD_DCE_RXD") (pintype "bidirectional"))
      (node (ref "U3") (pin "10") (pinfunction "T2IN_10") (pintype "input"))
    )
    (net (code "75") (name "VUSB") (class "Default")
      (node (ref "D4") (pin "A") (pinfunction "A_A") (pintype "passive"))
    )
    (net (code "76") (name "unconnected-(HUAWEI-PLC1-PadNC)") (class "Default")
      (node (ref "HUAWEI-PLC1") (pin "NC") (pinfunction "NC_NC") (pintype "bidirectional"))
    )
    (net (code "77") (name "unconnected-(HUAWEI-PLC1-PadNC1)") (class "Default")
      (node (ref "HUAWEI-PLC1") (pin "NC1") (pinfunction "NC1_NC1") (pintype "bidirectional"))
    )
    (net (code "78") (name "unconnected-(HUAWEI-PLC1-PadNC2)") (class "Default")
      (node (ref "HUAWEI-PLC1") (pin "NC2") (pinfunction "NC2_NC2") (pintype "bidirectional"))
    )
    (net (code "79") (name "unconnected-(HUAWEI-PLC1-PadNC3)") (class "Default")
      (node (ref "HUAWEI-PLC1") (pin "NC3") (pinfunction "NC3_NC3") (pintype "bidirectional"))
    )
    (net (code "80") (name "unconnected-(HUAWEI-PLC1-PadNC4)") (class "Default")
      (node (ref "HUAWEI-PLC1") (pin "NC4") (pinfunction "NC4_NC4") (pintype "bidirectional"))
    )
    (net (code "81") (name "unconnected-(HUAWEI-PLC1-PadNC5)") (class "Default")
      (node (ref "HUAWEI-PLC1") (pin "NC5") (pinfunction "NC5_NC5") (pintype "bidirectional"))
    )
    (net (code "82") (name "unconnected-(HUAWEI-PLC1-PadNC6)") (class "Default")
      (node (ref "HUAWEI-PLC1") (pin "NC6") (pinfunction "NC6_NC6") (pintype "bidirectional"))
    )
    (net (code "83") (name "unconnected-(HUAWEI-PLC1-PadNC7)") (class "Default")
      (node (ref "HUAWEI-PLC1") (pin "NC7") (pinfunction "NC7_NC7") (pintype "bidirectional"))
    )
    (net (code "84") (name "unconnected-(HUAWEI-PLC1-PadNC8)") (class "Default")
      (node (ref "HUAWEI-PLC1") (pin "NC8") (pinfunction "NC8_NC8") (pintype "bidirectional"))
    )
    (net (code "85") (name "unconnected-(HUAWEI-PLC1-PadNC9)") (class "Default")
      (node (ref "HUAWEI-PLC1") (pin "NC9") (pinfunction "NC9_NC9") (pintype "bidirectional"))
    )
    (net (code "86") (name "unconnected-(HUAWEI-PLC1-PadNC10)") (class "Default")
      (node (ref "HUAWEI-PLC1") (pin "NC10") (pinfunction "NC10_NC10") (pintype "bidirectional"))
    )
    (net (code "87") (name "unconnected-(HUAWEI-PLC1-PadNC11)") (class "Default")
      (node (ref "HUAWEI-PLC1") (pin "NC11") (pinfunction "NC11_NC11") (pintype "bidirectional"))
    )
    (net (code "88") (name "unconnected-(HUAWEI-PLC1-PadNC12)") (class "Default")
      (node (ref "HUAWEI-PLC1") (pin "NC12") (pinfunction "NC12_NC12") (pintype "bidirectional"))
    )
    (net (code "89") (name "unconnected-(HUAWEI-PLC1-PadNC13)") (class "Default")
      (node (ref "HUAWEI-PLC1") (pin "NC13") (pinfunction "NC13_NC13") (pintype "bidirectional"))
    )
    (net (code "90") (name "unconnected-(HUAWEI-PLC1-PadNC14)") (class "Default")
      (node (ref "HUAWEI-PLC1") (pin "NC14") (pinfunction "NC14_NC14") (pintype "bidirectional"))
    )
    (net (code "91") (name "unconnected-(HUAWEI-PLC1-PadNC15)") (class "Default")
      (node (ref "HUAWEI-PLC1") (pin "NC15") (pinfunction "NC15_NC15") (pintype "bidirectional"))
    )
    (net (code "92") (name "unconnected-(HUAWEI-PLC1-PadNC16)") (class "Default")
      (node (ref "HUAWEI-PLC1") (pin "NC16") (pinfunction "NC16_NC16") (pintype "bidirectional"))
    )
    (net (code "93") (name "unconnected-(HUAWEI-PLC1-PadNC17)") (class "Default")
      (node (ref "HUAWEI-PLC1") (pin "NC17") (pinfunction "NC17_NC17") (pintype "bidirectional"))
    )
    (net (code "94") (name "unconnected-(HUAWEI-PLC1-PadNC18)") (class "Default")
      (node (ref "HUAWEI-PLC1") (pin "NC18") (pinfunction "NC18_NC18") (pintype "bidirectional"))
    )
    (net (code "95") (name "unconnected-(HUAWEI-PLC1-PadNC19)") (class "Default")
      (node (ref "HUAWEI-PLC1") (pin "NC19") (pinfunction "NC19_NC19") (pintype "bidirectional"))
    )
    (net (code "96") (name "unconnected-(HUAWEI-PLC1-PadNC20)") (class "Default")
      (node (ref "HUAWEI-PLC1") (pin "NC20") (pinfunction "NC20_NC20") (pintype "bidirectional"))
    )
    (net (code "97") (name "unconnected-(HUAWEI-PLC1-PadNC21)") (class "Default")
      (node (ref "HUAWEI-PLC1") (pin "NC21") (pinfunction "NC21_NC21") (pintype "bidirectional"))
    )
    (net (code "98") (name "unconnected-(HUAWEI-PLC1-PadNC22)") (class "Default")
      (node (ref "HUAWEI-PLC1") (pin "NC22") (pinfunction "NC22_NC22") (pintype "bidirectional"))
    )
    (net (code "99") (name "unconnected-(HUAWEI-PLC1-PadNC23)") (class "Default")
      (node (ref "HUAWEI-PLC1") (pin "NC23") (pinfunction "NC23_NC23") (pintype "bidirectional"))
    )
    (net (code "100") (name "unconnected-(HUAWEI-PLC1-PadRD+)") (class "Default")
      (node (ref "HUAWEI-PLC1") (pin "RD+") (pinfunction "RD+_RD+") (pintype "bidirectional"))
    )
    (net (code "101") (name "unconnected-(HUAWEI-PLC1-PadRD-)") (class "Default")
      (node (ref "HUAWEI-PLC1") (pin "RD-") (pinfunction "RD-_RD-") (pintype "bidirectional"))
    )
    (net (code "102") (name "unconnected-(HUAWEI-PLC1-PadRST)") (class "Default")
      (node (ref "HUAWEI-PLC1") (pin "RST") (pinfunction "RST_RST") (pintype "bidirectional"))
    )
    (net (code "103") (name "unconnected-(HUAWEI-PLC1-PadSTATE0)") (class "Default")
      (node (ref "HUAWEI-PLC1") (pin "STATE0") (pinfunction "STATE0_STATE0") (pintype "bidirectional"))
    )
    (net (code "104") (name "unconnected-(HUAWEI-PLC1-PadTD+)") (class "Default")
      (node (ref "HUAWEI-PLC1") (pin "TD+") (pinfunction "TD+_TD+") (pintype "bidirectional"))
    )
    (net (code "105") (name "unconnected-(HUAWEI-PLC1-PadTD-)") (class "Default")
      (node (ref "HUAWEI-PLC1") (pin "TD-") (pinfunction "TD-_TD-") (pintype "bidirectional"))
    )
    (net (code "106") (name "unconnected-(J1-Pad2)") (class "Default")
      (node (ref "J1") (pin "2") (pinfunction "2_2") (pintype "passive"))
    )
    (net (code "107") (name "unconnected-(J3-Pad2)") (class "Default")
      (node (ref "J3") (pin "2") (pinfunction "2_2") (pintype "passive"))
    )
    (net (code "108") (name "unconnected-(J3-Pad4)") (class "Default")
      (node (ref "J3") (pin "4") (pinfunction "4_4") (pintype "passive"))
    )
    (net (code "109") (name "unconnected-(J7-Pad2)") (class "Default")
      (node (ref "J7") (pin "2") (pinfunction "2_2") (pintype "passive"))
    )
    (net (code "110") (name "unconnected-(J8-Pad2)") (class "Default")
      (node (ref "J8") (pin "2") (pinfunction "2_2") (pintype "passive"))
    )
    (net (code "111") (name "unconnected-(J9-Pad2)") (class "Default")
      (node (ref "J9") (pin "2") (pinfunction "2_2") (pintype "passive"))
    )
    (net (code "112") (name "unconnected-(J9-Pad4)") (class "Default")
      (node (ref "J9") (pin "4") (pinfunction "4_4") (pintype "passive"))
    )
    (net (code "113") (name "unconnected-(POWERMETER1-PadG)") (class "Default")
      (node (ref "POWERMETER1") (pin "G") (pinfunction "G_G") (pintype "bidirectional"))
    )
    (net (code "114") (name "unconnected-(POWERMETER1-PadS)") (class "Default")
      (node (ref "POWERMETER1") (pin "S") (pinfunction "S_S") (pintype "bidirectional"))
    )
    (net (code "115") (name "unconnected-(U3-R1IN-Pad13)") (class "Default")
      (node (ref "U3") (pin "13") (pinfunction "R1IN_13") (pintype "input"))
    )
    (net (code "116") (name "unconnected-(U3-R1OUT-Pad12)") (class "Default")
      (node (ref "U3") (pin "12") (pinfunction "R1OUT_12") (pintype "output"))
    )
    (net (code "117") (name "unconnected-(U3-T1IN-Pad11)") (class "Default")
      (node (ref "U3") (pin "11") (pinfunction "T1IN_11") (pintype "input"))
    )
    (net (code "118") (name "unconnected-(U3-T1OUT-Pad14)") (class "Default")
      (node (ref "U3") (pin "14") (pinfunction "T1OUT_14") (pintype "output"))
    )
  )
)
